# flasher.net
KiCad netlist of a schematic drawn in EAGLE
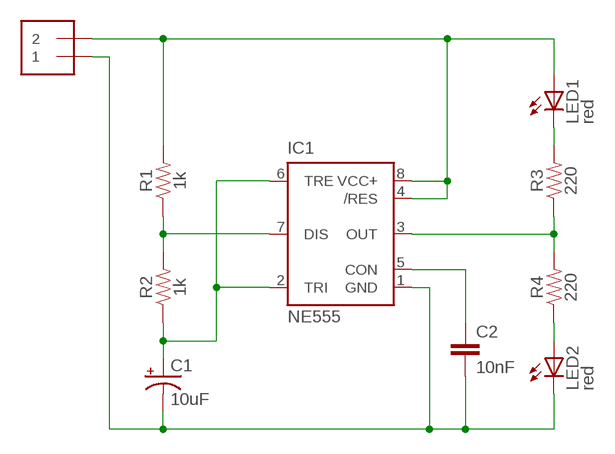
[diagram p0: schematic, sheet 1]

(export (version "E")
  (design (tool "Eeschema 10.0.6"))
  (components
    (comp (ref "C1")
      (value "10uF")
      (footprint "eagle-import:CPOL-RADIAL-2.5MM-5MM")
      (libsource (lib "eagle-import") (part "10UF-POLAR-RADIAL-2.5MM-25V-20%"))
    )
    (comp (ref "C2")
      (value "10nF")
      (footprint "eagle-import:0603")
      (libsource (lib "eagle-import") (part "10NF-0603-50V-10%"))
    )
    (comp (ref "IC1")
      (value "NE555")
      (footprint "eagle-import:DIL-08")
      (fields (field (name "MF") "Arrow Electronics") (field (name "MPN") "NE555N"))
      (libsource (lib "eagle-import") (part "NE555"))
    )
    (comp (ref "J1")
      (value "1X2-3.5MM")
      (footprint "eagle-import:1X2-3.5MM")
      (libsource (lib "eagle-import") (part "1X2-3.5MM"))
    )
    (comp (ref "LED1")
      (value "red")
      (footprint "eagle-import:LED5MM")
      (libsource (lib "eagle-import") (part "LED5MM"))
    )
    (comp (ref "LED2")
      (value "red")
      (footprint "eagle-import:LED5MM")
      (libsource (lib "eagle-import") (part "LED5MM"))
    )
    (comp (ref "R1")
      (value "1k")
      (footprint "eagle-import:AXIAL-0.3")
      (libsource (lib "eagle-import") (part "RESISTORAXIAL-0.3"))
    )
    (comp (ref "R2")
      (value "1k")
      (footprint "eagle-import:AXIAL-0.3")
      (libsource (lib "eagle-import") (part "RESISTORAXIAL-0.3"))
    )
    (comp (ref "R3")
      (value "220")
      (footprint "eagle-import:AXIAL-0.3")
      (libsource (lib "eagle-import") (part "RESISTORAXIAL-0.3"))
    )
    (comp (ref "R4")
      (value "220")
      (footprint "eagle-import:AXIAL-0.3")
      (libsource (lib "eagle-import") (part "RESISTORAXIAL-0.3"))
    )
  )
  (nets
    (net (code "1") (name "Net-(C1-+)") (class "Default")
      (node (ref "C1") (pin "1") (pinfunction "+_1") (pintype "passive"))
      (node (ref "IC1") (pin "2") (pinfunction "TRI_2") (pintype "input"))
      (node (ref "IC1") (pin "6") (pinfunction "TRE_6") (pintype "input"))
      (node (ref "R2") (pin "P$1") (pinfunction "1_P$1") (pintype "passive"))
    )
    (net (code "2") (name "Net-(C1--)") (class "Default")
      (node (ref "C1") (pin "2") (pinfunction "-_2") (pintype "passive"))
      (node (ref "C2") (pin "2") (pinfunction "2_2") (pintype "passive"))
      (node (ref "IC1") (pin "1") (pinfunction "GND_1") (pintype "power_in"))
      (node (ref "J1") (pin "1") (pinfunction "1_1") (pintype "passive"))
      (node (ref "LED2") (pin "K") (pinfunction "C_K") (pintype "passive"))
    )
    (net (code "3") (name "Net-(IC1-CON)") (class "Default")
      (node (ref "C2") (pin "1") (pinfunction "1_1") (pintype "passive"))
      (node (ref "IC1") (pin "5") (pinfunction "CON_5") (pintype "input"))
    )
    (net (code "4") (name "Net-(IC1-DIS)") (class "Default")
      (node (ref "IC1") (pin "7") (pinfunction "DIS_7") (pintype "input"))
      (node (ref "R1") (pin "P$1") (pinfunction "1_P$1") (pintype "passive"))
      (node (ref "R2") (pin "P$2") (pinfunction "2_P$2") (pintype "passive"))
    )
    (net (code "5") (name "Net-(IC1-OUT)") (class "Default")
      (node (ref "IC1") (pin "3") (pinfunction "OUT_3") (pintype "output"))
      (node (ref "R3") (pin "P$1") (pinfunction "1_P$1") (pintype "passive"))
      (node (ref "R4") (pin "P$2") (pinfunction "2_P$2") (pintype "passive"))
    )
    (net (code "6") (name "Net-(IC1-VCC+)") (class "Default")
      (node (ref "IC1") (pin "4") (pinfunction "/RES_4") (pintype "input"))
      (node (ref "IC1") (pin "8") (pinfunction "VCC+_8") (pintype "power_in"))
      (node (ref "J1") (pin "2") (pinfunction "2_2") (pintype "passive"))
      (node (ref "LED1") (pin "A") (pinfunction "A_A") (pintype "passive"))
      (node (ref "R1") (pin "P$2") (pinfunction "2_P$2") (pintype "passive"))
    )
    (net (code "7") (name "Net-(LED1-C)") (class "Default")
      (node (ref "LED1") (pin "K") (pinfunction "C_K") (pintype "passive"))
      (node (ref "R3") (pin "P$2") (pinfunction "2_P$2") (pintype "passive"))
    )
    (net (code "8") (name "Net-(R4-1)") (class "Default")
      (node (ref "LED2") (pin "A") (pinfunction "A_A") (pintype "passive"))
      (node (ref "R4") (pin "P$1") (pinfunction "1_P$1") (pintype "passive"))
    )
  )
)
